# 20A_DC_Motor_Controller_with_SLAVE_OUT_v.net
KiCad netlist of a schematic drawn in EAGLE
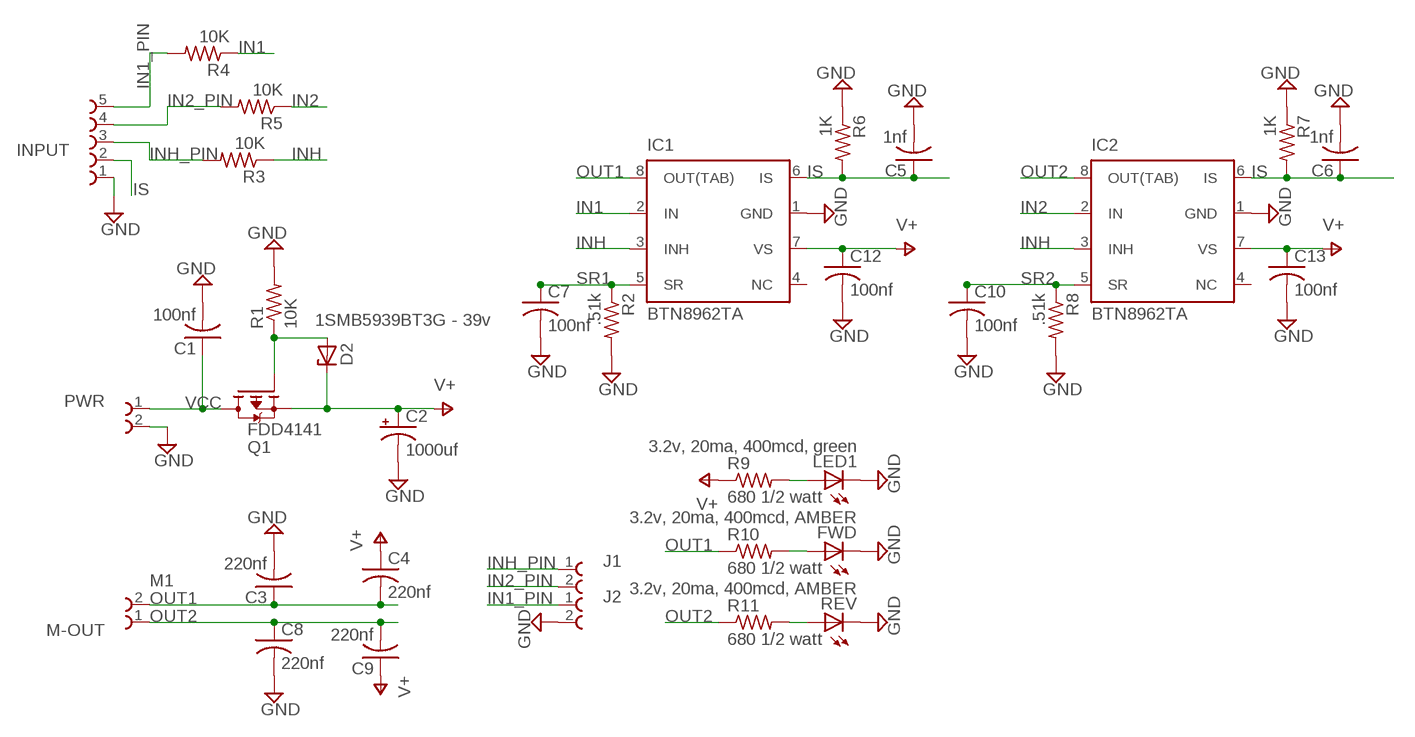
[diagram p0: schematic, sheet 1]

(export (version "E")
  (design (tool "Eeschema 10.0.6"))
  (components
    (comp (ref "C1")
      (value "100nf")
      (footprint "eagle-import:C0805")
      (libsource (lib "eagle-import") (part "C-USC0805"))
    )
    (comp (ref "C2")
      (value "1000uf")
      (footprint "eagle-import:TT5D10")
      (libsource (lib "eagle-import") (part "CPOL-USTT5D10"))
    )
    (comp (ref "C3")
      (value "220nf")
      (footprint "eagle-import:C0805")
      (libsource (lib "eagle-import") (part "C-USC0805"))
    )
    (comp (ref "C4")
      (value "220nf")
      (footprint "eagle-import:C0805")
      (libsource (lib "eagle-import") (part "C-USC0805"))
    )
    (comp (ref "C5")
      (value "1nf")
      (footprint "eagle-import:C0805")
      (libsource (lib "eagle-import") (part "C-USC0805"))
    )
    (comp (ref "C6")
      (value "1nf")
      (footprint "eagle-import:C0805")
      (libsource (lib "eagle-import") (part "C-USC0805"))
    )
    (comp (ref "C7")
      (value "100nf")
      (footprint "eagle-import:C0805")
      (libsource (lib "eagle-import") (part "C-USC0805"))
    )
    (comp (ref "C8")
      (value "220nf")
      (footprint "eagle-import:C0805")
      (libsource (lib "eagle-import") (part "C-USC0805"))
    )
    (comp (ref "C9")
      (value "220nf")
      (footprint "eagle-import:C0805")
      (libsource (lib "eagle-import") (part "C-USC0805"))
    )
    (comp (ref "C10")
      (value "100nf")
      (footprint "eagle-import:C0805")
      (libsource (lib "eagle-import") (part "C-USC0805"))
    )
    (comp (ref "C12")
      (value "100nf")
      (footprint "eagle-import:C0805")
      (libsource (lib "eagle-import") (part "C-USC0805"))
    )
    (comp (ref "C13")
      (value "100nf")
      (footprint "eagle-import:C0805")
      (libsource (lib "eagle-import") (part "C-USC0805"))
    )
    (comp (ref "D2")
      (value "1SMB5939BT3G - 39v")
      (footprint "eagle-import:SMB")
      (libsource (lib "eagle-import") (part "ZENER-DIODESMB"))
    )
    (comp (ref "FWD")
      (value "3.2v, 20ma, 400mcd, AMBER")
      (footprint "eagle-import:CHIPLED_0805")
      (libsource (lib "eagle-import") (part "LEDCHIPLED_0805"))
    )
    (comp (ref "IC1")
      (value "BTN8962TA")
      (footprint "eagle-import:P-TO263-7-1_LG_PADS")
      (libsource (lib "eagle-import") (part "BTN8962TA"))
    )
    (comp (ref "IC2")
      (value "BTN8962TA")
      (footprint "eagle-import:P-TO263-7-1_LG_PADS")
      (libsource (lib "eagle-import") (part "BTN8962TA"))
    )
    (comp (ref "INPUT")
      (value "691311500105")
      (footprint "eagle-import:691311500105")
      (libsource (lib "eagle-import") (part "691311500105"))
    )
    (comp (ref "J1")
      (value "WURTH_ELEKTRONIK_ELECTROMECHANIC_TERMINAL_BLOCKS_CONNECTORS_REV16E_691214110002")
      (footprint "eagle-import:WURTH_ELEKTRONIK_ELECTROMECHANIC_TERMINAL_BLOCKS_CONNECTORS_REV16E_691214110002")
      (libsource (lib "eagle-import") (part "WURTH_ELEKTRONIK_ELECTROMECHANIC_TERMINAL_BLOCKS_CONNECTORS_REV16E_691214110002"))
    )
    (comp (ref "J2")
      (value "WURTH_ELEKTRONIK_ELECTROMECHANIC_TERMINAL_BLOCKS_CONNECTORS_REV16E_691214110002")
      (footprint "eagle-import:WURTH_ELEKTRONIK_ELECTROMECHANIC_TERMINAL_BLOCKS_CONNECTORS_REV16E_691214110002")
      (libsource (lib "eagle-import") (part "WURTH_ELEKTRONIK_ELECTROMECHANIC_TERMINAL_BLOCKS_CONNECTORS_REV16E_691214110002"))
    )
    (comp (ref "LED1")
      (value "3.2v, 20ma, 400mcd, green")
      (footprint "eagle-import:CHIPLED_0805")
      (libsource (lib "eagle-import") (part "LEDCHIPLED_0805"))
    )
    (comp (ref "M-OUT")
      (value "TERMINAL BLOCK 7.50MM VERT 2POS, ED110/2DS")
      (footprint "eagle-import:7-5MM-SCREW-TERM")
      (libsource (lib "eagle-import") (part "7-5MM-SCREW-TERM"))
    )
    (comp (ref "PWR")
      (value "TERMINAL BLOCK 7.50MM VERT 2POS, ED110/2DS")
      (footprint "eagle-import:7-5MM-SCREW-TERM")
      (libsource (lib "eagle-import") (part "7-5MM-SCREW-TERM"))
    )
    (comp (ref "Q1")
      (value "FDD4141")
      (footprint "eagle-import:TO252")
      (libsource (lib "eagle-import") (part "FDD4141TO252"))
    )
    (comp (ref "R1")
      (value "10K")
      (footprint "eagle-import:R0805")
      (libsource (lib "eagle-import") (part "R-US_R0805"))
    )
    (comp (ref "R2")
      (value ".51k")
      (footprint "eagle-import:R0805")
      (libsource (lib "eagle-import") (part "R-US_R0805"))
    )
    (comp (ref "R3")
      (value "10K")
      (footprint "eagle-import:R0805")
      (libsource (lib "eagle-import") (part "R-US_R0805"))
    )
    (comp (ref "R4")
      (value "10K")
      (footprint "eagle-import:R0805")
      (libsource (lib "eagle-import") (part "R-US_R0805"))
    )
    (comp (ref "R5")
      (value "10K")
      (footprint "eagle-import:R0805")
      (libsource (lib "eagle-import") (part "R-US_R0805"))
    )
    (comp (ref "R6")
      (value "1K")
      (footprint "eagle-import:R0805")
      (libsource (lib "eagle-import") (part "R-US_R0805"))
    )
    (comp (ref "R7")
      (value "1K")
      (footprint "eagle-import:R0805")
      (libsource (lib "eagle-import") (part "R-US_R0805"))
    )
    (comp (ref "R8")
      (value ".51k")
      (footprint "eagle-import:R0805")
      (libsource (lib "eagle-import") (part "R-US_R0805"))
    )
    (comp (ref "R9")
      (value "680 1/2 watt")
      (footprint "eagle-import:R0805")
      (libsource (lib "eagle-import") (part "R-US_R0805"))
    )
    (comp (ref "R10")
      (value "680 1/2 watt")
      (footprint "eagle-import:R0805")
      (libsource (lib "eagle-import") (part "R-US_R0805"))
    )
    (comp (ref "R11")
      (value "680 1/2 watt")
      (footprint "eagle-import:R0805")
      (libsource (lib "eagle-import") (part "R-US_R0805"))
    )
    (comp (ref "REV")
      (value "3.2v, 20ma, 400mcd, AMBER")
      (footprint "eagle-import:CHIPLED_0805")
      (libsource (lib "eagle-import") (part "LEDCHIPLED_0805"))
    )
  )
  (nets
    (net (code "1") (name "/IN1") (class "Default")
      (node (ref "IC1") (pin "2") (pinfunction "IN_2") (pintype "input"))
      (node (ref "R4") (pin "1") (pinfunction "1_1") (pintype "passive"))
    )
    (net (code "2") (name "/IN1_PIN") (class "Default")
      (node (ref "INPUT") (pin "5") (pinfunction "5_5") (pintype "passive"))
      (node (ref "J2") (pin "1") (pinfunction "1_1") (pintype "passive"))
      (node (ref "R4") (pin "2") (pinfunction "2_2") (pintype "passive"))
    )
    (net (code "3") (name "/IN2") (class "Default")
      (node (ref "IC2") (pin "2") (pinfunction "IN_2") (pintype "input"))
      (node (ref "R5") (pin "1") (pinfunction "1_1") (pintype "passive"))
    )
    (net (code "4") (name "/IN2_PIN") (class "Default")
      (node (ref "INPUT") (pin "4") (pinfunction "4_4") (pintype "passive"))
      (node (ref "J1") (pin "2") (pinfunction "2_2") (pintype "passive"))
      (node (ref "R5") (pin "2") (pinfunction "2_2") (pintype "passive"))
    )
    (net (code "5") (name "/INH") (class "Default")
      (node (ref "IC1") (pin "3") (pinfunction "INH_3") (pintype "input"))
      (node (ref "IC2") (pin "3") (pinfunction "INH_3") (pintype "input"))
      (node (ref "R3") (pin "1") (pinfunction "1_1") (pintype "passive"))
    )
    (net (code "6") (name "/INH_PIN") (class "Default")
      (node (ref "INPUT") (pin "3") (pinfunction "3_3") (pintype "passive"))
      (node (ref "J1") (pin "1") (pinfunction "1_1") (pintype "passive"))
      (node (ref "R3") (pin "2") (pinfunction "2_2") (pintype "passive"))
    )
    (net (code "7") (name "/IS") (class "Default")
      (node (ref "C5") (pin "1") (pinfunction "1_1") (pintype "passive"))
      (node (ref "C6") (pin "1") (pinfunction "1_1") (pintype "passive"))
      (node (ref "IC1") (pin "6") (pinfunction "IS_6") (pintype "output"))
      (node (ref "IC2") (pin "6") (pinfunction "IS_6") (pintype "output"))
      (node (ref "INPUT") (pin "2") (pinfunction "2_2") (pintype "passive"))
      (node (ref "R6") (pin "2") (pinfunction "2_2") (pintype "passive"))
      (node (ref "R7") (pin "2") (pinfunction "2_2") (pintype "passive"))
    )
    (net (code "8") (name "/OUT1") (class "Default")
      (node (ref "C3") (pin "1") (pinfunction "1_1") (pintype "passive"))
      (node (ref "C4") (pin "2") (pinfunction "2_2") (pintype "passive"))
      (node (ref "IC1") (pin "8") (pinfunction "OUT(TAB)_8") (pintype "output"))
      (node (ref "M-OUT") (pin "2") (pinfunction "2_2") (pintype "passive"))
      (node (ref "R10") (pin "1") (pinfunction "1_1") (pintype "passive"))
    )
    (net (code "9") (name "/OUT2") (class "Default")
      (node (ref "C8") (pin "1") (pinfunction "1_1") (pintype "passive"))
      (node (ref "C9") (pin "2") (pinfunction "2_2") (pintype "passive"))
      (node (ref "IC2") (pin "8") (pinfunction "OUT(TAB)_8") (pintype "output"))
      (node (ref "M-OUT") (pin "1") (pinfunction "1_1") (pintype "passive"))
      (node (ref "R11") (pin "1") (pinfunction "1_1") (pintype "passive"))
    )
    (net (code "10") (name "/SR1") (class "Default")
      (node (ref "C7") (pin "1") (pinfunction "1_1") (pintype "passive"))
      (node (ref "IC1") (pin "5") (pinfunction "SR_5") (pintype "input"))
      (node (ref "R2") (pin "1") (pinfunction "1_1") (pintype "passive"))
    )
    (net (code "11") (name "/SR2") (class "Default")
      (node (ref "C10") (pin "1") (pinfunction "1_1") (pintype "passive"))
      (node (ref "IC2") (pin "5") (pinfunction "SR_5") (pintype "input"))
      (node (ref "R8") (pin "1") (pinfunction "1_1") (pintype "passive"))
    )
    (net (code "12") (name "/VCC") (class "Default")
      (node (ref "C1") (pin "1") (pinfunction "1_1") (pintype "passive"))
      (node (ref "PWR") (pin "1") (pinfunction "1_1") (pintype "passive"))
      (node (ref "Q1") (pin "3") (pinfunction "D_3") (pintype "passive"))
    )
    (net (code "13") (name "GND") (class "Default")
      (node (ref "C1") (pin "2") (pinfunction "2_2") (pintype "passive"))
      (node (ref "C10") (pin "2") (pinfunction "2_2") (pintype "passive"))
      (node (ref "C12") (pin "2") (pinfunction "2_2") (pintype "passive"))
      (node (ref "C13") (pin "2") (pinfunction "2_2") (pintype "passive"))
      (node (ref "C2") (pin "-") (pinfunction "-_-") (pintype "passive"))
      (node (ref "C3") (pin "2") (pinfunction "2_2") (pintype "passive"))
      (node (ref "C5") (pin "2") (pinfunction "2_2") (pintype "passive"))
      (node (ref "C6") (pin "2") (pinfunction "2_2") (pintype "passive"))
      (node (ref "C7") (pin "2") (pinfunction "2_2") (pintype "passive"))
      (node (ref "C8") (pin "2") (pinfunction "2_2") (pintype "passive"))
      (node (ref "FWD") (pin "C") (pinfunction "C_C") (pintype "passive"))
      (node (ref "IC1") (pin "1") (pinfunction "GND_1") (pintype "power_in"))
      (node (ref "IC2") (pin "1") (pinfunction "GND_1") (pintype "power_in"))
      (node (ref "INPUT") (pin "1") (pinfunction "1_1") (pintype "passive"))
      (node (ref "J2") (pin "2") (pinfunction "2_2") (pintype "passive"))
      (node (ref "LED1") (pin "C") (pinfunction "C_C") (pintype "passive"))
      (node (ref "PWR") (pin "2") (pinfunction "2_2") (pintype "passive"))
      (node (ref "R1") (pin "2") (pinfunction "2_2") (pintype "passive"))
      (node (ref "R2") (pin "2") (pinfunction "2_2") (pintype "passive"))
      (node (ref "R6") (pin "1") (pinfunction "1_1") (pintype "passive"))
      (node (ref "R7") (pin "1") (pinfunction "1_1") (pintype "passive"))
      (node (ref "R8") (pin "2") (pinfunction "2_2") (pintype "passive"))
      (node (ref "REV") (pin "C") (pinfunction "C_C") (pintype "passive"))
    )
    (net (code "14") (name "Net-(FWD-PadA)") (class "Default")
      (node (ref "FWD") (pin "A") (pinfunction "A_A") (pintype "passive"))
      (node (ref "R10") (pin "2") (pinfunction "2_2") (pintype "passive"))
    )
    (net (code "15") (name "Net-(LED1-PadA)") (class "Default")
      (node (ref "LED1") (pin "A") (pinfunction "A_A") (pintype "passive"))
      (node (ref "R9") (pin "2") (pinfunction "2_2") (pintype "passive"))
    )
    (net (code "16") (name "Net-(Q1-G)") (class "Default")
      (node (ref "D2") (pin "A") (pinfunction "A_A") (pintype "passive"))
      (node (ref "Q1") (pin "1") (pinfunction "G_1") (pintype "passive"))
      (node (ref "R1") (pin "1") (pinfunction "1_1") (pintype "passive"))
    )
    (net (code "17") (name "Net-(R11-Pad2)") (class "Default")
      (node (ref "R11") (pin "2") (pinfunction "2_2") (pintype "passive"))
      (node (ref "REV") (pin "A") (pinfunction "A_A") (pintype "passive"))
    )
    (net (code "18") (name "V+") (class "Default")
      (node (ref "C12") (pin "1") (pinfunction "1_1") (pintype "passive"))
      (node (ref "C13") (pin "1") (pinfunction "1_1") (pintype "passive"))
      (node (ref "C2") (pin "+") (pinfunction "+_+") (pintype "passive"))
      (node (ref "C4") (pin "1") (pinfunction "1_1") (pintype "passive"))
      (node (ref "C9") (pin "1") (pinfunction "1_1") (pintype "passive"))
      (node (ref "D2") (pin "C") (pinfunction "C_C") (pintype "passive"))
      (node (ref "IC1") (pin "7") (pinfunction "VS_7") (pintype "power_in"))
      (node (ref "IC2") (pin "7") (pinfunction "VS_7") (pintype "power_in"))
      (node (ref "Q1") (pin "2") (pinfunction "S_2") (pintype "passive"))
      (node (ref "R9") (pin "1") (pinfunction "1_1") (pintype "passive"))
    )
    (net (code "19") (name "unconnected-(IC1-NC-Pad4)") (class "Default")
      (node (ref "IC1") (pin "4") (pinfunction "NC_4") (pintype "no_connect"))
    )
    (net (code "20") (name "unconnected-(IC2-NC-Pad4)") (class "Default")
      (node (ref "IC2") (pin "4") (pinfunction "NC_4") (pintype "no_connect"))
    )
  )
)
